# Sunfish_ECU_Sensor_RevA.net
KiCad netlist of a schematic drawn in Altium Designer
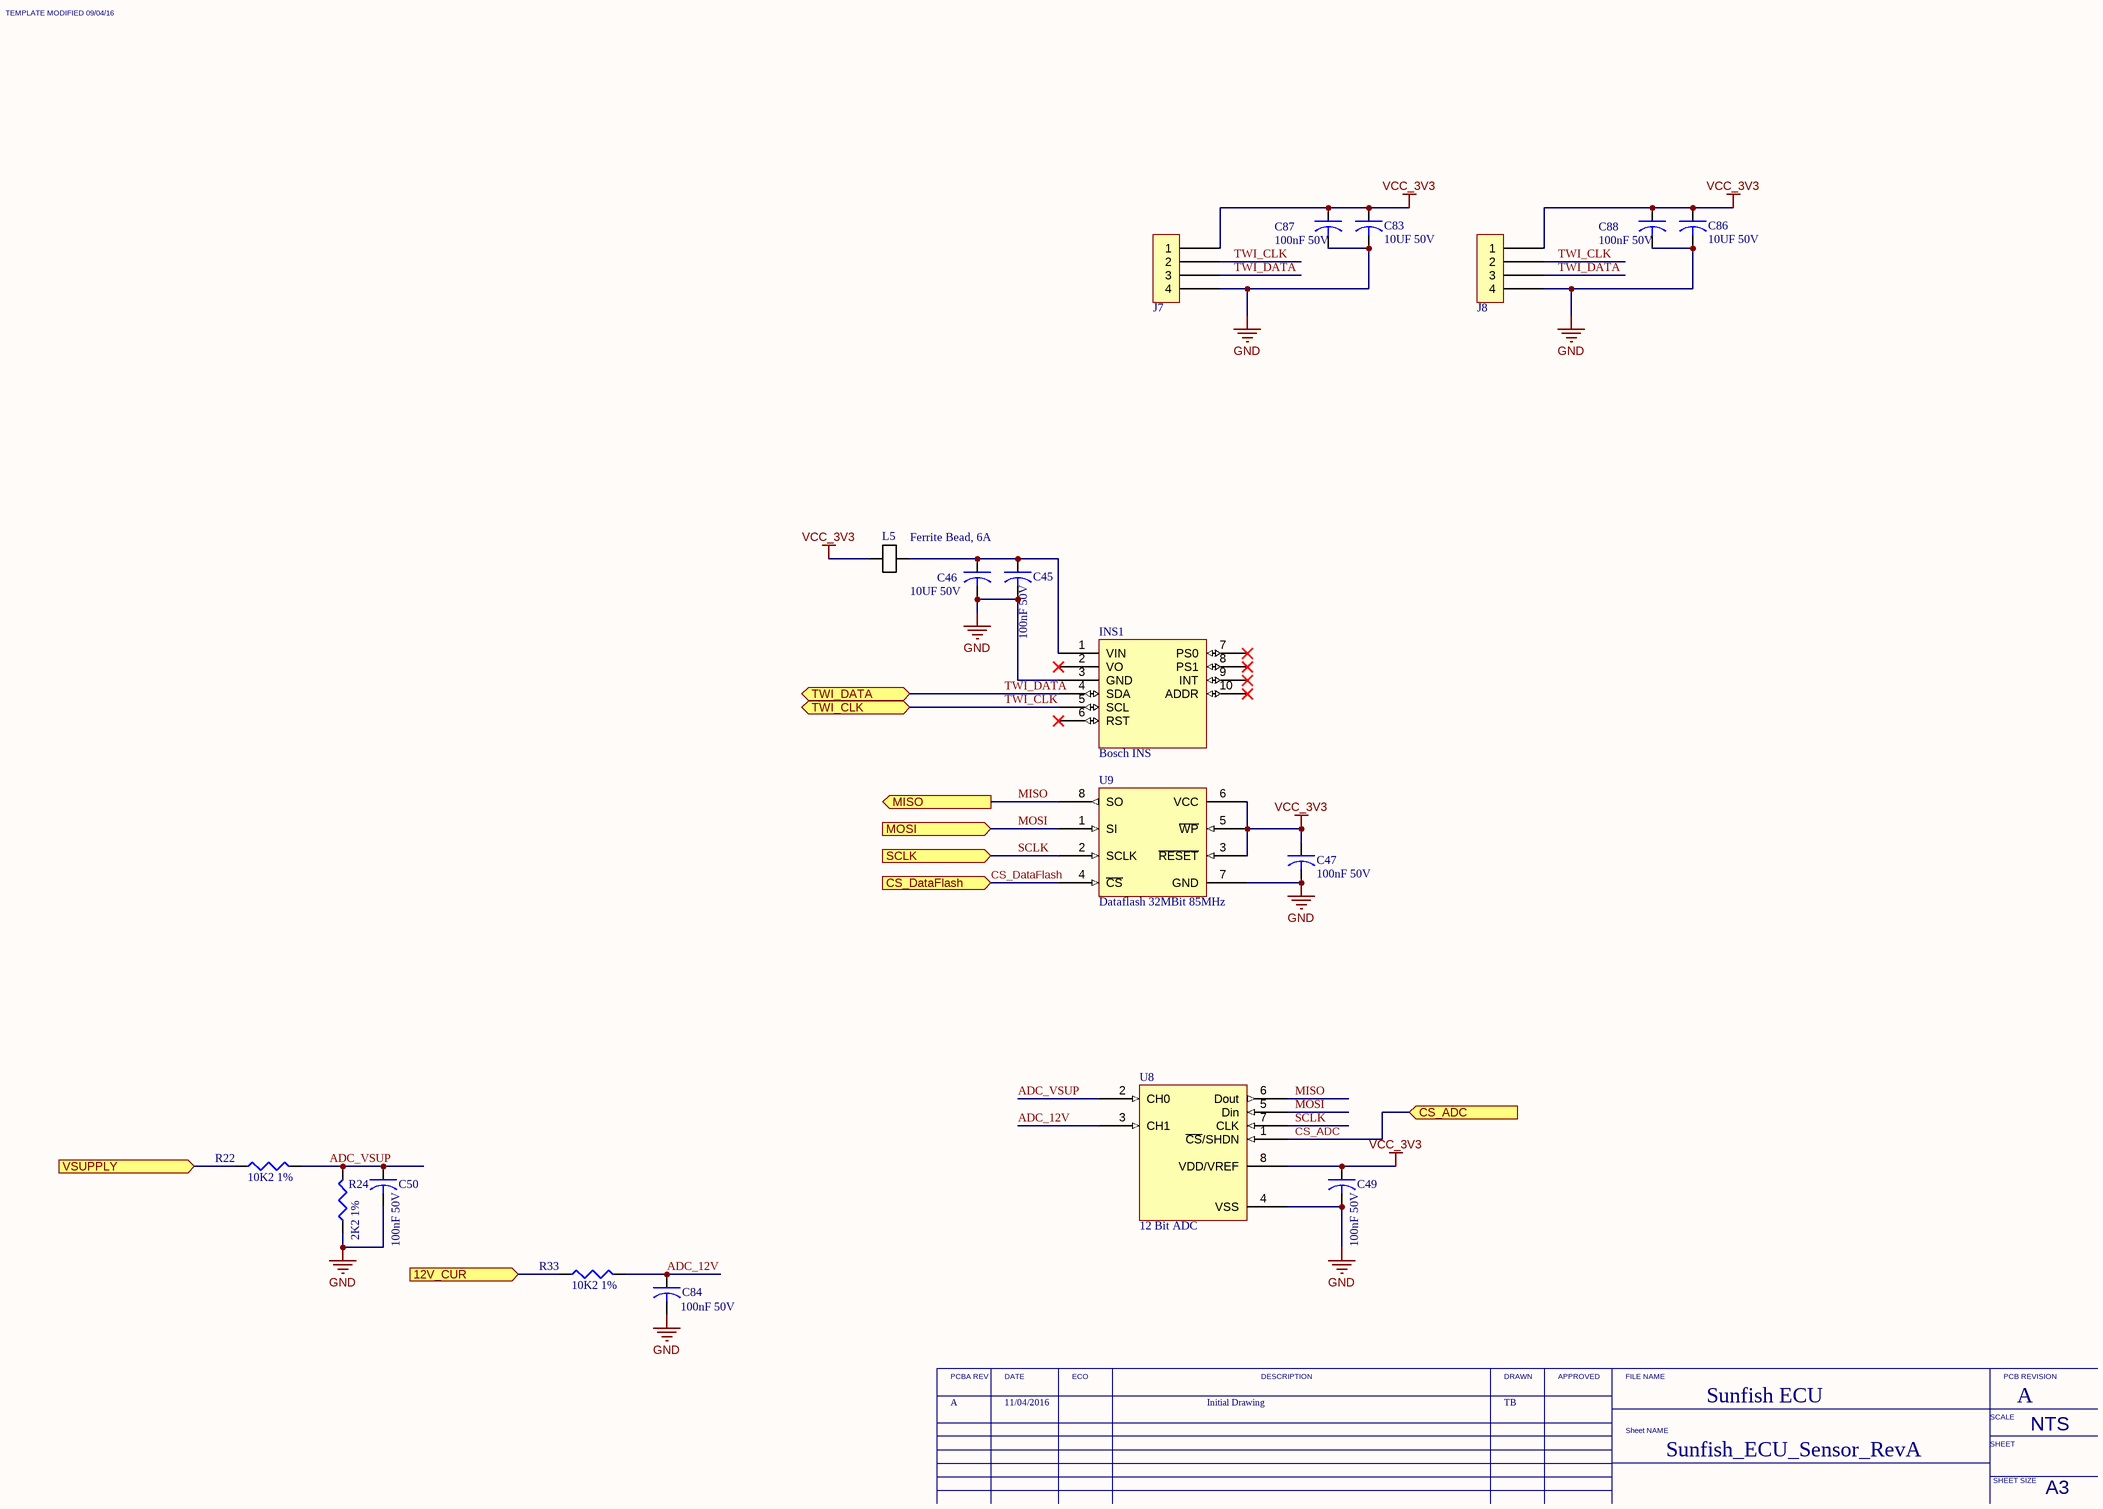
[diagram p0: Sunfish_ECU_Sensor_RevA.SchDoc]

(export (version "E")
  (design (tool "Eeschema 10.0.6"))
  (components
    (comp (ref "C45")
      (value "100nF 50V")
      (footprint "0603")
      (description "CAP CER 100nF 50V 10% X7R 0603")
      (fields (field (name "MANUFACTURER") "Murata"))
      (libsource (lib "") (part "CAP_100NF_50V_10%_0603_1"))
    )
    (comp (ref "C46")
      (value "10UF 50V")
      (footprint "1206")
      (description "CAP CER 10UF 50V 10% X5R 1206")
      (fields (field (name "MANUFACTURER") "Murata"))
      (libsource (lib "") (part "CAP_10UF_50V_10%_1206_1"))
    )
    (comp (ref "C47")
      (value "100nF 50V")
      (footprint "0603")
      (description "CAP CER 100nF 50V 10% X7R 0603")
      (fields (field (name "MANUFACTURER") "Murata"))
      (libsource (lib "ThrusterControl") (part "CAP_100NF_50V_10%_0603"))
    )
    (comp (ref "C49")
      (value "100nF 50V")
      (footprint "0603")
      (description "CAP CER 100nF 50V 10% X7R 0603")
      (fields (field (name "MANUFACTURER") "Murata"))
      (libsource (lib "") (part "CAP_100NF_50V_10%_0603_1"))
    )
    (comp (ref "C50")
      (value "100nF 50V")
      (footprint "0603")
      (description "CAP CER 100nF 50V 10% X7R 0603")
      (fields (field (name "MANUFACTURER") "Murata"))
      (libsource (lib "") (part "CAP_100NF_50V_10%_0603_1"))
    )
    (comp (ref "C83")
      (value "10UF 50V")
      (footprint "1206")
      (description "CAP CER 10UF 50V 10% X5R 1206")
      (fields (field (name "MANUFACTURER") "Murata"))
      (libsource (lib "ThrusterControl") (part "CAP_10UF_50V_10%_1206"))
    )
    (comp (ref "C84")
      (value "100nF 50V")
      (footprint "0603")
      (description "CAP CER 100nF 50V 10% X7R 0603")
      (fields (field (name "MANUFACTURER") "Murata"))
      (libsource (lib "") (part "CAP_100NF_50V_10%_0603_1"))
    )
    (comp (ref "C86")
      (value "10UF 50V")
      (footprint "1206")
      (description "CAP CER 10UF 50V 10% X5R 1206")
      (fields (field (name "MANUFACTURER") "Murata"))
      (libsource (lib "ThrusterControl") (part "CAP_10UF_50V_10%_1206"))
    )
    (comp (ref "C87")
      (value "100nF 50V")
      (footprint "0603")
      (description "CAP CER 100nF 50V 10% X7R 0603")
      (fields (field (name "MANUFACTURER") "Murata"))
      (libsource (lib "Caps") (part "CAP_100NF_50V_10%_0603"))
    )
    (comp (ref "C88")
      (value "100nF 50V")
      (footprint "0603")
      (description "CAP CER 100nF 50V 10% X7R 0603")
      (fields (field (name "MANUFACTURER") "Murata"))
      (libsource (lib "Caps") (part "CAP_100NF_50V_10%_0603"))
    )
    (comp (ref "INS1")
      (value "Bosch INS")
      (footprint "IC_INC_BNO055")
      (libsource (lib "Hardware") (part "IC_INS_BNO055"))
    )
    (comp (ref "J7")
      (value "4 Positions Header, Shrouded Connector 0.049\" (1.25mm) Through Hole Tin")
      (footprint "DF13-4P-1.25DSA")
      (description "CON_4_Pos_Header")
      (fields (field (name "MANUFACTURER") "Hirose Electric Co Ltd"))
      (libsource (lib "Hardware") (part "CON_4_Pos_Header"))
    )
    (comp (ref "J8")
      (value "4 Positions Header, Shrouded Connector 0.049\" (1.25mm) Through Hole Tin")
      (footprint "DF13-4P-1.25DSA")
      (description "CON_4_Pos_Header")
      (fields (field (name "MANUFACTURER") "Hirose Electric Co Ltd"))
      (libsource (lib "Hardware") (part "CON_4_Pos_Header"))
    )
    (comp (ref "L5")
      (value "Ferrite Bead, 6A")
      (footprint "1806")
      (fields (field (name "MANUFACTURER") "MURATA"))
      (libsource (lib "Inductors") (part "IND_FERRITE_ BLM41PG600SN1L"))
    )
    (comp (ref "R22")
      (value "10K2 1%")
      (footprint "0603")
      (description "Resistor, 10K2, 1%, 0603")
      (fields (field (name "MANUFACTURER") "Yageo"))
      (libsource (lib "Resistors") (part "RES_10K2_1%_0603"))
    )
    (comp (ref "R24")
      (value "2K2 1%")
      (footprint "0603")
      (description "Resistor, 2K2, 1%, 0603")
      (fields (field (name "MANUFACTURER") "Bourns Inc"))
      (libsource (lib "PowerDistributor") (part "RES_2K2_1%_0603"))
    )
    (comp (ref "R33")
      (value "10K2 1%")
      (footprint "0603")
      (description "Resistor, 10K2, 1%, 0603")
      (fields (field (name "MANUFACTURER") "Yageo"))
      (libsource (lib "Resistors") (part "RES_10K2_1%_0603"))
    )
    (comp (ref "U8")
      (value "12 Bit ADC")
      (footprint "SO-8")
      (description "MCP3202, 12 Bit, 2 CH ADC")
      (fields (field (name "MANUFACTURER") "Microchip"))
      (libsource (lib "IC") (part "IC_ADC_MCP3202"))
    )
    (comp (ref "U9")
      (value "Dataflash 32MBit 85MHz")
      (footprint "SOIC127P800X216-8M")
      (description "IC DATAFLASH 32MB 85MHZ 8SOIC")
      (fields (field (name "MANUFACTURER") "Adesto Technologies"))
      (libsource (lib "IC") (part "IC_Dataflash_32MBit"))
    )
  )
  (nets
    (net (code "1") (name "/12V_CUR") (class "Default") (node (ref "R33") (pin "1") (pintype "passive")))
    (net (code "2") (name "/ADC_12V") (class "Default")
      (node (ref "C84") (pin "1") (pinfunction "1_1") (pintype "passive"))
      (node (ref "R33") (pin "2") (pintype "passive"))
      (node (ref "U8") (pin "3") (pinfunction "CH1_3") (pintype "input"))
    )
    (net (code "3") (name "/ADC_VSUP") (class "Default")
      (node (ref "C50") (pin "1") (pinfunction "1_1") (pintype "passive"))
      (node (ref "R22") (pin "2") (pintype "passive"))
      (node (ref "R24") (pin "2") (pintype "passive"))
      (node (ref "U8") (pin "2") (pinfunction "CH0_2") (pintype "input"))
    )
    (net (code "4") (name "/CS_ADC") (class "Default")
      (node (ref "U8") (pin "1") (pinfunction "~{CS}/SHDN_1") (pintype "input"))
    )
    (net (code "5") (name "/CS_DataFlash") (class "Default")
      (node (ref "U9") (pin "4") (pinfunction "~{CS}_4") (pintype "input"))
    )
    (net (code "6") (name "/MISO") (class "Default")
      (node (ref "U8") (pin "6") (pinfunction "Dout_6") (pintype "output"))
      (node (ref "U9") (pin "8") (pinfunction "SO_8") (pintype "output"))
    )
    (net (code "7") (name "/MOSI") (class "Default")
      (node (ref "U8") (pin "5") (pinfunction "Din_5") (pintype "input"))
      (node (ref "U9") (pin "1") (pinfunction "SI_1") (pintype "input"))
    )
    (net (code "8") (name "/SCLK") (class "Default")
      (node (ref "U8") (pin "7") (pinfunction "CLK_7") (pintype "input"))
      (node (ref "U9") (pin "2") (pinfunction "SCLK_2") (pintype "input"))
    )
    (net (code "9") (name "/TWI_CLK") (class "Default")
      (node (ref "INS1") (pin "5") (pinfunction "SCL_5") (pintype "bidirectional"))
      (node (ref "J7") (pin "2") (pinfunction "2_2") (pintype "power_in"))
      (node (ref "J8") (pin "2") (pinfunction "2_2") (pintype "power_in"))
    )
    (net (code "10") (name "/TWI_DATA") (class "Default")
      (node (ref "INS1") (pin "4") (pinfunction "SDA_4") (pintype "bidirectional"))
      (node (ref "J7") (pin "3") (pinfunction "3_3") (pintype "power_in"))
      (node (ref "J8") (pin "3") (pinfunction "3_3") (pintype "power_in"))
    )
    (net (code "11") (name "/VSUPPLY") (class "Default") (node (ref "R22") (pin "1") (pintype "passive")))
    (net (code "12") (name "GND") (class "Default")
      (node (ref "C45") (pin "2") (pinfunction "2_2") (pintype "passive"))
      (node (ref "C46") (pin "2") (pinfunction "2_2") (pintype "passive"))
      (node (ref "C47") (pin "2") (pinfunction "2_2") (pintype "passive"))
      (node (ref "C49") (pin "2") (pinfunction "2_2") (pintype "passive"))
      (node (ref "C50") (pin "2") (pinfunction "2_2") (pintype "passive"))
      (node (ref "C83") (pin "2") (pinfunction "2_2") (pintype "passive"))
      (node (ref "C84") (pin "2") (pinfunction "2_2") (pintype "passive"))
      (node (ref "C86") (pin "2") (pinfunction "2_2") (pintype "passive"))
      (node (ref "C87") (pin "2") (pinfunction "2_2") (pintype "passive"))
      (node (ref "C88") (pin "2") (pinfunction "2_2") (pintype "passive"))
      (node (ref "INS1") (pin "3") (pinfunction "GND_3") (pintype "power_in"))
      (node (ref "J7") (pin "4") (pinfunction "4_4") (pintype "power_in"))
      (node (ref "J8") (pin "4") (pinfunction "4_4") (pintype "power_in"))
      (node (ref "R24") (pin "1") (pintype "passive"))
      (node (ref "U8") (pin "4") (pinfunction "VSS_4") (pintype "power_in"))
      (node (ref "U9") (pin "7") (pinfunction "GND_7") (pintype "power_in"))
    )
    (net (code "13") (name "Net-(INS1-VIN)") (class "Default")
      (node (ref "C45") (pin "1") (pinfunction "1_1") (pintype "passive"))
      (node (ref "C46") (pin "1") (pinfunction "1_1") (pintype "passive"))
      (node (ref "INS1") (pin "1") (pinfunction "VIN_1") (pintype "power_in"))
      (node (ref "L5") (pin "2") (pinfunction "2_2") (pintype "passive"))
    )
    (net (code "14") (name "VCC_3V3") (class "Default")
      (node (ref "C47") (pin "1") (pinfunction "1_1") (pintype "passive"))
      (node (ref "C49") (pin "1") (pinfunction "1_1") (pintype "passive"))
      (node (ref "C83") (pin "1") (pinfunction "1_1") (pintype "passive"))
      (node (ref "C86") (pin "1") (pinfunction "1_1") (pintype "passive"))
      (node (ref "C87") (pin "1") (pinfunction "1_1") (pintype "passive"))
      (node (ref "C88") (pin "1") (pinfunction "1_1") (pintype "passive"))
      (node (ref "J7") (pin "1") (pinfunction "1_1") (pintype "power_in"))
      (node (ref "J8") (pin "1") (pinfunction "1_1") (pintype "power_in"))
      (node (ref "L5") (pin "1") (pinfunction "1_1") (pintype "passive"))
      (node (ref "U8") (pin "8") (pinfunction "VDD/VREF_8") (pintype "power_in"))
      (node (ref "U9") (pin "3") (pinfunction "~{RESET}_3") (pintype "input"))
      (node (ref "U9") (pin "5") (pinfunction "~{WP}_5") (pintype "input"))
      (node (ref "U9") (pin "6") (pinfunction "VCC_6") (pintype "power_in"))
    )
    (net (code "15") (name "unconnected-(INS1-ADDR-Pad10)") (class "Default")
      (node (ref "INS1") (pin "10") (pinfunction "ADDR_10") (pintype "bidirectional+no_connect"))
    )
    (net (code "16") (name "unconnected-(INS1-INT-Pad9)") (class "Default")
      (node (ref "INS1") (pin "9") (pinfunction "INT_9") (pintype "bidirectional+no_connect"))
    )
    (net (code "17") (name "unconnected-(INS1-PS0-Pad7)") (class "Default")
      (node (ref "INS1") (pin "7") (pinfunction "PS0_7") (pintype "bidirectional+no_connect"))
    )
    (net (code "18") (name "unconnected-(INS1-PS1-Pad8)") (class "Default")
      (node (ref "INS1") (pin "8") (pinfunction "PS1_8") (pintype "bidirectional+no_connect"))
    )
    (net (code "19") (name "unconnected-(INS1-RST-Pad6)") (class "Default")
      (node (ref "INS1") (pin "6") (pinfunction "RST_6") (pintype "bidirectional+no_connect"))
    )
    (net (code "20") (name "unconnected-(INS1-VO-Pad2)") (class "Default")
      (node (ref "INS1") (pin "2") (pinfunction "VO_2") (pintype "power_in+no_connect"))
    )
  )
)
